# Qwiic_Switch-Gap-0_0320.net
KiCad netlist of a schematic drawn in EAGLE
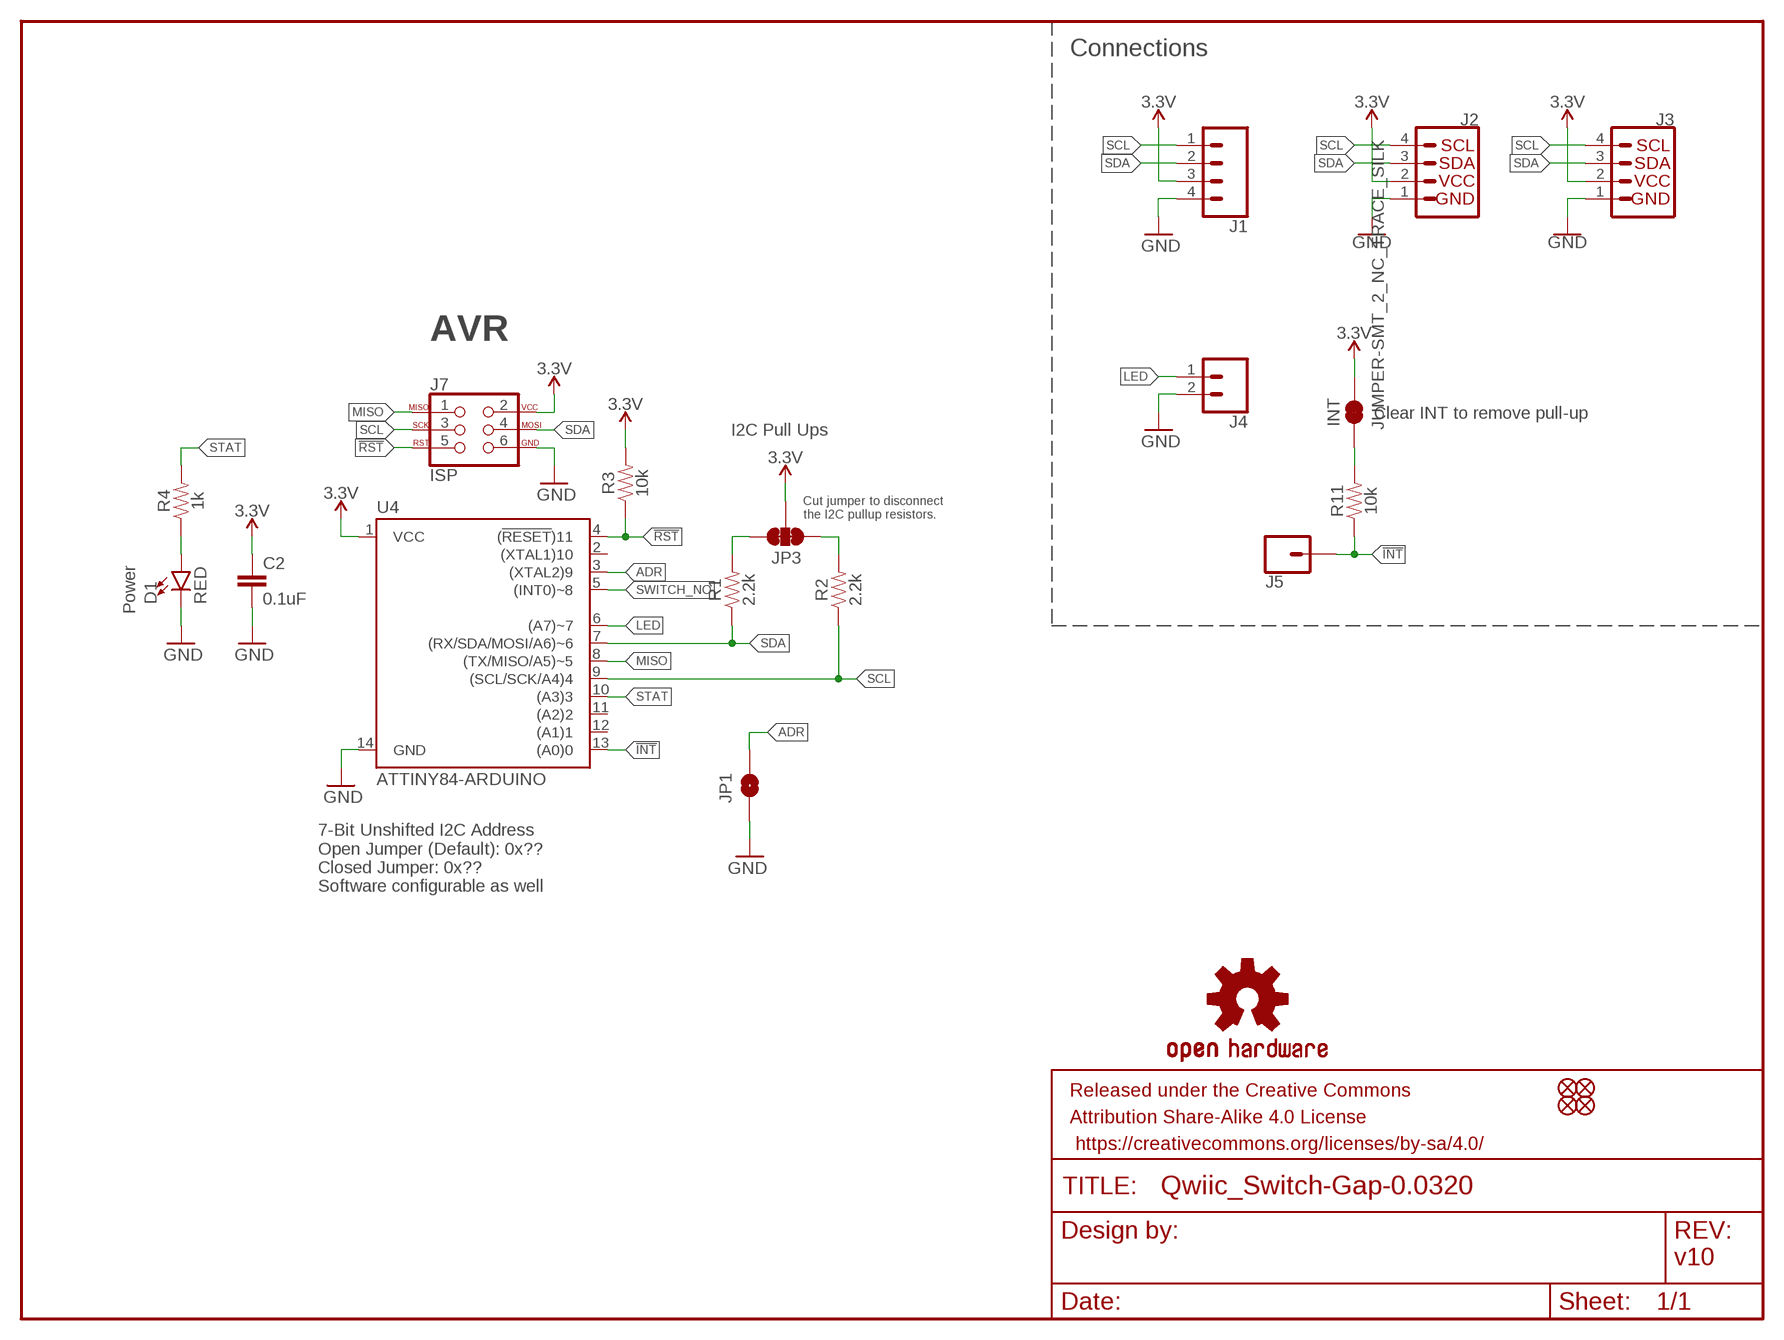
[diagram p0: schematic, sheet 1]

(export (version "E")
  (design (tool "Eeschema 10.0.6"))
  (components
    (comp (ref "C2")
      (value "0.1uF")
      (footprint "eagle-import:0603")
      (libsource (lib "eagle-import") (part "0.1UF-0603-25V-(+80/-20%)"))
    )
    (comp (ref "D1")
      (value "RED")
      (footprint "eagle-import:LED-0603")
      (libsource (lib "eagle-import") (part "LED-RED0603"))
    )
    (comp (ref "FRAME1")
      (value "FRAME-LETTER")
      (footprint "eagle-import:CREATIVE_COMMONS")
      (libsource (lib "eagle-import") (part "FRAME-LETTER"))
    )
    (comp (ref "INT")
      (value "JUMPER-SMT_2_NC_TRACE_SILK")
      (footprint "eagle-import:SMT-JUMPER_2_NC_TRACE_SILK")
      (libsource (lib "eagle-import") (part "JUMPER-SMT_2_NC_TRACE_SILK"))
    )
    (comp (ref "J1")
      (value "CONN_041X04_NO_SILK")
      (footprint "eagle-import:1X04_NO_SILK")
      (libsource (lib "eagle-import") (part "CONN_041X04_NO_SILK"))
    )
    (comp (ref "J2")
      (value "QWIIC_CONNECTORJS-1MM")
      (footprint "eagle-import:JST04_1MM_RA")
      (libsource (lib "eagle-import") (part "QWIIC_CONNECTORJS-1MM"))
    )
    (comp (ref "J3")
      (value "QWIIC_CONNECTORJS-1MM")
      (footprint "eagle-import:JST04_1MM_RA")
      (libsource (lib "eagle-import") (part "QWIIC_CONNECTORJS-1MM"))
    )
    (comp (ref "J4")
      (value "CONN_021X02_NO_SILK")
      (footprint "eagle-import:1X02_NO_SILK")
      (libsource (lib "eagle-import") (part "CONN_021X02_NO_SILK"))
    )
    (comp (ref "J5")
      (value "CONN_01PTH_NO_SILK_YES_STOP")
      (footprint "eagle-import:1X01_NO_SILK")
      (libsource (lib "eagle-import") (part "CONN_01PTH_NO_SILK_YES_STOP"))
    )
    (comp (ref "J7")
      (value "ISP")
      (footprint "eagle-import:2X3_TEST_POINTS")
      (libsource (lib "eagle-import") (part "AVR_SPI_PROG_3X2TESTPOINTS"))
    )
    (comp (ref "JP1")
      (value "JUMPER-SMT_2_NO_SILK")
      (footprint "eagle-import:SMT-JUMPER_2_NO_SILK")
      (libsource (lib "eagle-import") (part "JUMPER-SMT_2_NO_SILK"))
    )
    (comp (ref "JP2")
      (value "FIDUCIALUFIDUCIAL")
      (footprint "eagle-import:MICRO-FIDUCIAL")
      (libsource (lib "eagle-import") (part "FIDUCIALUFIDUCIAL"))
    )
    (comp (ref "JP3")
      (value "JUMPER-SMT_3_2-NC_TRACE_SILK")
      (footprint "eagle-import:SMT-JUMPER_3_2-NC_TRACE_SILK")
      (libsource (lib "eagle-import") (part "JUMPER-SMT_3_2-NC_TRACE_SILK"))
    )
    (comp (ref "JP6")
      (value "FIDUCIALUFIDUCIAL")
      (footprint "eagle-import:MICRO-FIDUCIAL")
      (libsource (lib "eagle-import") (part "FIDUCIALUFIDUCIAL"))
    )
    (comp (ref "JP8")
      (value "FIDUCIALUFIDUCIAL")
      (footprint "eagle-import:MICRO-FIDUCIAL")
      (libsource (lib "eagle-import") (part "FIDUCIALUFIDUCIAL"))
    )
    (comp (ref "JP9")
      (value "FIDUCIALUFIDUCIAL")
      (footprint "eagle-import:MICRO-FIDUCIAL")
      (libsource (lib "eagle-import") (part "FIDUCIALUFIDUCIAL"))
    )
    (comp (ref "LOGO1")
      (value "OSHW-LOGOMINI")
      (footprint "eagle-import:OSHW-LOGO-MINI")
      (libsource (lib "eagle-import") (part "OSHW-LOGOMINI"))
    )
    (comp (ref "R1")
      (value "2.2k")
      (footprint "eagle-import:0603")
      (libsource (lib "eagle-import") (part "2.2KOHM-0603-1/10W-1%"))
    )
    (comp (ref "R2")
      (value "2.2k")
      (footprint "eagle-import:0603")
      (libsource (lib "eagle-import") (part "2.2KOHM-0603-1/10W-1%"))
    )
    (comp (ref "R3")
      (value "10k")
      (footprint "eagle-import:0603")
      (libsource (lib "eagle-import") (part "10KOHM-0603-1/10W-1%"))
    )
    (comp (ref "R4")
      (value "1k")
      (footprint "eagle-import:0603")
      (libsource (lib "eagle-import") (part "1KOHM-0603-1/10W-1%"))
    )
    (comp (ref "R11")
      (value "10k")
      (footprint "eagle-import:0603")
      (libsource (lib "eagle-import") (part "10KOHM-0603-1/10W-1%"))
    )
    (comp (ref "U4")
      (value "ATTINY84-ARDUINO")
      (footprint "eagle-import:SO14")
      (libsource (lib "eagle-import") (part "ATTINY84-ARDUINO"))
    )
  )
  (nets
    (net (code "1") (name "/~{INT}") (class "Default")
      (node (ref "J5") (pin "1") (pinfunction "1_1") (pintype "passive"))
      (node (ref "R11") (pin "1") (pinfunction "1_1") (pintype "passive"))
      (node (ref "U4") (pin "13") (pinfunction "(A0)0_13") (pintype "bidirectional"))
    )
    (net (code "2") (name "/~{RST}") (class "Default")
      (node (ref "J7") (pin "5") (pinfunction "5_5") (pintype "passive"))
      (node (ref "R3") (pin "1") (pinfunction "1_1") (pintype "passive"))
      (node (ref "U4") (pin "4") (pinfunction "(~{RESET})11_4") (pintype "bidirectional"))
    )
    (net (code "3") (name "3.3V") (class "Default")
      (node (ref "C2") (pin "1") (pinfunction "1_1") (pintype "passive"))
      (node (ref "INT") (pin "2") (pinfunction "2_2") (pintype "passive"))
      (node (ref "J1") (pin "3") (pinfunction "3_3") (pintype "passive"))
      (node (ref "J2") (pin "2") (pinfunction "2_2") (pintype "power_in"))
      (node (ref "J3") (pin "2") (pinfunction "2_2") (pintype "power_in"))
      (node (ref "J7") (pin "2") (pinfunction "2_2") (pintype "passive"))
      (node (ref "JP3") (pin "2") (pinfunction "2_2") (pintype "passive"))
      (node (ref "R3") (pin "2") (pinfunction "2_2") (pintype "passive"))
      (node (ref "U4") (pin "1") (pinfunction "VCC_1") (pintype "bidirectional"))
    )
    (net (code "4") (name "ADR") (class "Default")
      (node (ref "JP1") (pin "2") (pinfunction "2_2") (pintype "passive"))
      (node (ref "U4") (pin "3") (pinfunction "(XTAL2)9_3") (pintype "bidirectional"))
    )
    (net (code "5") (name "GND") (class "Default")
      (node (ref "C2") (pin "2") (pinfunction "2_2") (pintype "passive"))
      (node (ref "D1") (pin "C") (pinfunction "C_C") (pintype "passive"))
      (node (ref "J1") (pin "4") (pinfunction "4_4") (pintype "passive"))
      (node (ref "J2") (pin "1") (pinfunction "1_1") (pintype "power_in"))
      (node (ref "J3") (pin "1") (pinfunction "1_1") (pintype "power_in"))
      (node (ref "J4") (pin "2") (pinfunction "2_2") (pintype "passive"))
      (node (ref "J7") (pin "6") (pinfunction "6_6") (pintype "passive"))
      (node (ref "JP1") (pin "1") (pinfunction "1_1") (pintype "passive"))
      (node (ref "U4") (pin "14") (pinfunction "GND_14") (pintype "bidirectional"))
    )
    (net (code "6") (name "LED") (class "Default")
      (node (ref "J4") (pin "1") (pinfunction "1_1") (pintype "passive"))
      (node (ref "U4") (pin "6") (pinfunction "(A7)~{7}_6") (pintype "bidirectional"))
    )
    (net (code "7") (name "MISO") (class "Default")
      (node (ref "J7") (pin "1") (pinfunction "1_1") (pintype "passive"))
      (node (ref "U4") (pin "8") (pinfunction "(TX/MISO/A5)~{5}_8") (pintype "bidirectional"))
    )
    (net (code "8") (name "Net-(D1-PadA)") (class "Default")
      (node (ref "D1") (pin "A") (pinfunction "A_A") (pintype "passive"))
      (node (ref "R4") (pin "1") (pinfunction "1_1") (pintype "passive"))
    )
    (net (code "9") (name "Net-(INT-Pad1)") (class "Default")
      (node (ref "INT") (pin "1") (pinfunction "1_1") (pintype "passive"))
      (node (ref "R11") (pin "2") (pinfunction "2_2") (pintype "passive"))
    )
    (net (code "10") (name "Net-(JP3-Pad1)") (class "Default")
      (node (ref "JP3") (pin "1") (pinfunction "1_1") (pintype "passive"))
      (node (ref "R2") (pin "2") (pinfunction "2_2") (pintype "passive"))
    )
    (net (code "11") (name "Net-(JP3-Pad3)") (class "Default")
      (node (ref "JP3") (pin "3") (pinfunction "3_3") (pintype "passive"))
      (node (ref "R1") (pin "2") (pinfunction "2_2") (pintype "passive"))
    )
    (net (code "12") (name "SCL") (class "Default")
      (node (ref "J1") (pin "1") (pinfunction "1_1") (pintype "passive"))
      (node (ref "J2") (pin "4") (pinfunction "4_4") (pintype "passive"))
      (node (ref "J3") (pin "4") (pinfunction "4_4") (pintype "passive"))
      (node (ref "J7") (pin "3") (pinfunction "3_3") (pintype "passive"))
      (node (ref "R2") (pin "1") (pinfunction "1_1") (pintype "passive"))
      (node (ref "U4") (pin "9") (pinfunction "(SCL/SCK/A4)4_9") (pintype "bidirectional"))
    )
    (net (code "13") (name "SDA") (class "Default")
      (node (ref "J1") (pin "2") (pinfunction "2_2") (pintype "passive"))
      (node (ref "J2") (pin "3") (pinfunction "3_3") (pintype "passive"))
      (node (ref "J3") (pin "3") (pinfunction "3_3") (pintype "passive"))
      (node (ref "J7") (pin "4") (pinfunction "4_4") (pintype "passive"))
      (node (ref "R1") (pin "1") (pinfunction "1_1") (pintype "passive"))
      (node (ref "U4") (pin "7") (pinfunction "(RX/SDA/MOSI/A6)~{6}_7") (pintype "bidirectional"))
    )
    (net (code "14") (name "STAT") (class "Default")
      (node (ref "R4") (pin "2") (pinfunction "2_2") (pintype "passive"))
      (node (ref "U4") (pin "10") (pinfunction "(A3)3_10") (pintype "bidirectional"))
    )
    (net (code "15") (name "SWITCH_NO") (class "Default")
      (node (ref "U4") (pin "5") (pinfunction "(INT0)~{8}_5") (pintype "bidirectional"))
    )
    (net (code "16") (name "unconnected-(U4-(A1)1-Pad12)") (class "Default")
      (node (ref "U4") (pin "12") (pinfunction "(A1)1_12") (pintype "bidirectional"))
    )
    (net (code "17") (name "unconnected-(U4-(A2)2-Pad11)") (class "Default")
      (node (ref "U4") (pin "11") (pinfunction "(A2)2_11") (pintype "bidirectional"))
    )
    (net (code "18") (name "unconnected-(U4-(XTAL1)10-Pad2)") (class "Default")
      (node (ref "U4") (pin "2") (pinfunction "(XTAL1)10_2") (pintype "bidirectional"))
    )
  )
)
